# nixieWatchV0.net
KiCad netlist of a schematic drawn in EAGLE
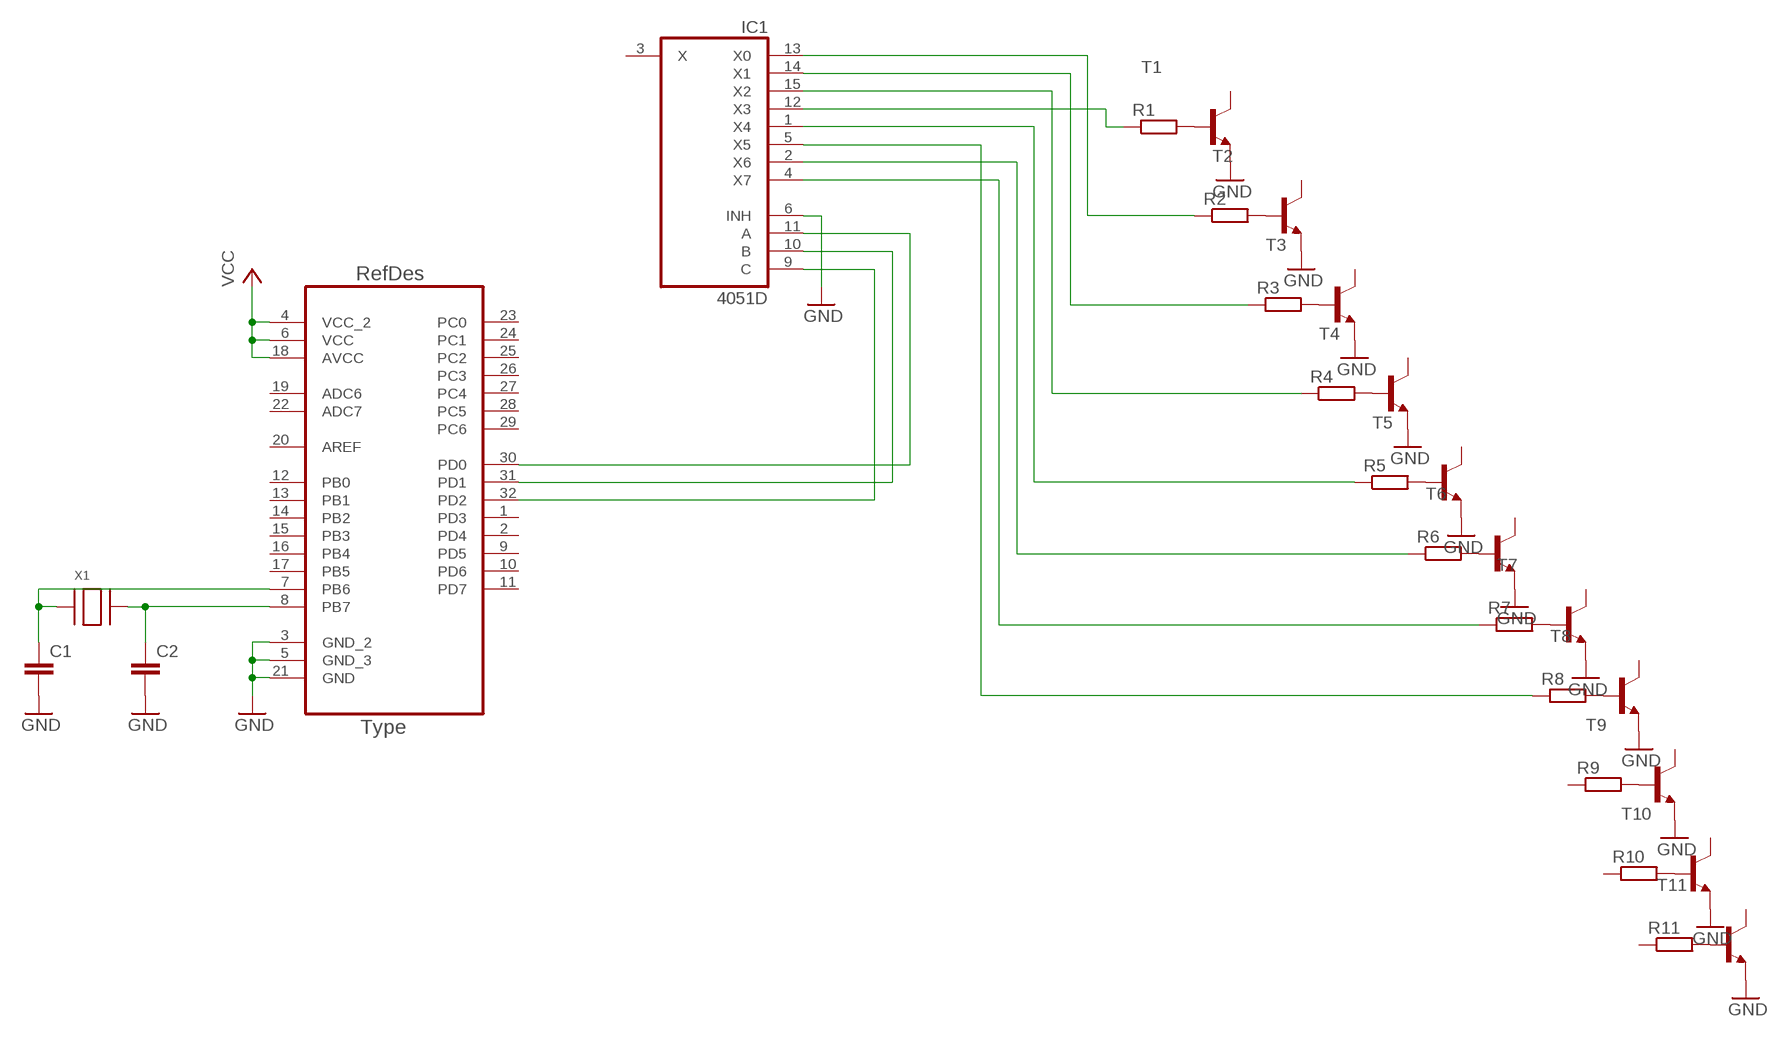
[diagram p0: schematic, sheet 1]

(export (version "E")
  (design (tool "Eeschema 10.0.6"))
  (components
    (comp (ref "C1")
      (value "C-EUC0402")
      (footprint "eagle-import:C0402")
      (libsource (lib "eagle-import") (part "C-EUC0402"))
    )
    (comp (ref "C2")
      (value "C-EUC0402")
      (footprint "eagle-import:C0402")
      (libsource (lib "eagle-import") (part "C-EUC0402"))
    )
    (comp (ref "IC1")
      (value "4051D")
      (footprint "eagle-import:SO16")
      (libsource (lib "eagle-import") (part "4051D"))
    )
    (comp (ref "R1")
      (value "R-EU_M1206")
      (footprint "eagle-import:M1206")
      (libsource (lib "eagle-import") (part "R-EU_M1206"))
    )
    (comp (ref "R2")
      (value "R-EU_M1206")
      (footprint "eagle-import:M1206")
      (libsource (lib "eagle-import") (part "R-EU_M1206"))
    )
    (comp (ref "R3")
      (value "R-EU_M1206")
      (footprint "eagle-import:M1206")
      (libsource (lib "eagle-import") (part "R-EU_M1206"))
    )
    (comp (ref "R4")
      (value "R-EU_M1206")
      (footprint "eagle-import:M1206")
      (libsource (lib "eagle-import") (part "R-EU_M1206"))
    )
    (comp (ref "R5")
      (value "R-EU_M1206")
      (footprint "eagle-import:M1206")
      (libsource (lib "eagle-import") (part "R-EU_M1206"))
    )
    (comp (ref "R6")
      (value "R-EU_M1206")
      (footprint "eagle-import:M1206")
      (libsource (lib "eagle-import") (part "R-EU_M1206"))
    )
    (comp (ref "R7")
      (value "R-EU_M1206")
      (footprint "eagle-import:M1206")
      (libsource (lib "eagle-import") (part "R-EU_M1206"))
    )
    (comp (ref "R8")
      (value "R-EU_M1206")
      (footprint "eagle-import:M1206")
      (libsource (lib "eagle-import") (part "R-EU_M1206"))
    )
    (comp (ref "R9")
      (value "R-EU_M1206")
      (footprint "eagle-import:M1206")
      (libsource (lib "eagle-import") (part "R-EU_M1206"))
    )
    (comp (ref "R10")
      (value "R-EU_M1206")
      (footprint "eagle-import:M1206")
      (libsource (lib "eagle-import") (part "R-EU_M1206"))
    )
    (comp (ref "R11")
      (value "R-EU_M1206")
      (footprint "eagle-import:M1206")
      (libsource (lib "eagle-import") (part "R-EU_M1206"))
    )
    (comp (ref "T1")
      (value "-NPN-SOT23-EBC")
      (footprint "eagle-import:SOT23-EBC")
      (libsource (lib "eagle-import") (part "-NPN-SOT23-EBC"))
    )
    (comp (ref "T2")
      (value "-NPN-SOT23-EBC")
      (footprint "eagle-import:SOT23-EBC")
      (libsource (lib "eagle-import") (part "-NPN-SOT23-EBC"))
    )
    (comp (ref "T3")
      (value "-NPN-SOT23-EBC")
      (footprint "eagle-import:SOT23-EBC")
      (libsource (lib "eagle-import") (part "-NPN-SOT23-EBC"))
    )
    (comp (ref "T4")
      (value "-NPN-SOT23-EBC")
      (footprint "eagle-import:SOT23-EBC")
      (libsource (lib "eagle-import") (part "-NPN-SOT23-EBC"))
    )
    (comp (ref "T5")
      (value "-NPN-SOT23-EBC")
      (footprint "eagle-import:SOT23-EBC")
      (libsource (lib "eagle-import") (part "-NPN-SOT23-EBC"))
    )
    (comp (ref "T6")
      (value "-NPN-SOT23-EBC")
      (footprint "eagle-import:SOT23-EBC")
      (libsource (lib "eagle-import") (part "-NPN-SOT23-EBC"))
    )
    (comp (ref "T7")
      (value "-NPN-SOT23-EBC")
      (footprint "eagle-import:SOT23-EBC")
      (libsource (lib "eagle-import") (part "-NPN-SOT23-EBC"))
    )
    (comp (ref "T8")
      (value "-NPN-SOT23-EBC")
      (footprint "eagle-import:SOT23-EBC")
      (libsource (lib "eagle-import") (part "-NPN-SOT23-EBC"))
    )
    (comp (ref "T9")
      (value "-NPN-SOT23-EBC")
      (footprint "eagle-import:SOT23-EBC")
      (libsource (lib "eagle-import") (part "-NPN-SOT23-EBC"))
    )
    (comp (ref "T10")
      (value "-NPN-SOT23-EBC")
      (footprint "eagle-import:SOT23-EBC")
      (libsource (lib "eagle-import") (part "-NPN-SOT23-EBC"))
    )
    (comp (ref "T11")
      (value "-NPN-SOT23-EBC")
      (footprint "eagle-import:SOT23-EBC")
      (libsource (lib "eagle-import") (part "-NPN-SOT23-EBC"))
    )
    (comp (ref "U1")
      (value "ATMEGA328P-AU")
      (footprint "eagle-import:QFP80P900X900X120-32N")
      (libsource (lib "eagle-import") (part "ATMEGA328P-AU"))
    )
    (comp (ref "X1")
      (value "XTAL-3.2X1.5")
      (footprint "eagle-import:XTAL3215")
      (libsource (lib "eagle-import") (part "XTAL-3.2X1.5"))
    )
  )
  (nets
    (net (code "1") (name "GND") (class "Default")
      (node (ref "C1") (pin "2") (pinfunction "2_2") (pintype "passive"))
      (node (ref "C2") (pin "2") (pinfunction "2_2") (pintype "passive"))
      (node (ref "IC1") (pin "6") (pinfunction "INH_6") (pintype "input"))
      (node (ref "T1") (pin "E") (pinfunction "E_E") (pintype "passive"))
      (node (ref "T10") (pin "E") (pinfunction "E_E") (pintype "passive"))
      (node (ref "T11") (pin "E") (pinfunction "E_E") (pintype "passive"))
      (node (ref "T2") (pin "E") (pinfunction "E_E") (pintype "passive"))
      (node (ref "T3") (pin "E") (pinfunction "E_E") (pintype "passive"))
      (node (ref "T4") (pin "E") (pinfunction "E_E") (pintype "passive"))
      (node (ref "T5") (pin "E") (pinfunction "E_E") (pintype "passive"))
      (node (ref "T6") (pin "E") (pinfunction "E_E") (pintype "passive"))
      (node (ref "T7") (pin "E") (pinfunction "E_E") (pintype "passive"))
      (node (ref "T8") (pin "E") (pinfunction "E_E") (pintype "passive"))
      (node (ref "T9") (pin "E") (pinfunction "E_E") (pintype "passive"))
      (node (ref "U1") (pin "21") (pinfunction "GND_21") (pintype "passive"))
      (node (ref "U1") (pin "3") (pinfunction "GND_2_3") (pintype "passive"))
      (node (ref "U1") (pin "5") (pinfunction "GND_3_5") (pintype "passive"))
    )
    (net (code "2") (name "Net-(IC1A-A)") (class "Default")
      (node (ref "IC1") (pin "11") (pinfunction "A_11") (pintype "input"))
      (node (ref "U1") (pin "30") (pinfunction "PD0_30") (pintype "bidirectional"))
    )
    (net (code "3") (name "Net-(IC1A-B)") (class "Default")
      (node (ref "IC1") (pin "10") (pinfunction "B_10") (pintype "input"))
      (node (ref "U1") (pin "31") (pinfunction "PD1_31") (pintype "bidirectional"))
    )
    (net (code "4") (name "Net-(IC1A-C)") (class "Default")
      (node (ref "IC1") (pin "9") (pinfunction "C_9") (pintype "input"))
      (node (ref "U1") (pin "32") (pinfunction "PD2_32") (pintype "bidirectional"))
    )
    (net (code "5") (name "Net-(IC1A-X0)") (class "Default")
      (node (ref "IC1") (pin "13") (pinfunction "X0_13") (pintype "bidirectional"))
      (node (ref "R2") (pin "1") (pinfunction "1_1") (pintype "passive"))
    )
    (net (code "6") (name "Net-(IC1A-X1)") (class "Default")
      (node (ref "IC1") (pin "14") (pinfunction "X1_14") (pintype "bidirectional"))
      (node (ref "R3") (pin "1") (pinfunction "1_1") (pintype "passive"))
    )
    (net (code "7") (name "Net-(IC1A-X2)") (class "Default")
      (node (ref "IC1") (pin "15") (pinfunction "X2_15") (pintype "bidirectional"))
      (node (ref "R4") (pin "1") (pinfunction "1_1") (pintype "passive"))
    )
    (net (code "8") (name "Net-(IC1A-X3)") (class "Default")
      (node (ref "IC1") (pin "12") (pinfunction "X3_12") (pintype "bidirectional"))
      (node (ref "R1") (pin "1") (pinfunction "1_1") (pintype "passive"))
    )
    (net (code "9") (name "Net-(IC1A-X4)") (class "Default")
      (node (ref "IC1") (pin "1") (pinfunction "X4_1") (pintype "bidirectional"))
      (node (ref "R5") (pin "1") (pinfunction "1_1") (pintype "passive"))
    )
    (net (code "10") (name "Net-(IC1A-X5)") (class "Default")
      (node (ref "IC1") (pin "5") (pinfunction "X5_5") (pintype "bidirectional"))
      (node (ref "R8") (pin "1") (pinfunction "1_1") (pintype "passive"))
    )
    (net (code "11") (name "Net-(IC1A-X6)") (class "Default")
      (node (ref "IC1") (pin "2") (pinfunction "X6_2") (pintype "bidirectional"))
      (node (ref "R6") (pin "1") (pinfunction "1_1") (pintype "passive"))
    )
    (net (code "12") (name "Net-(IC1A-X7)") (class "Default")
      (node (ref "IC1") (pin "4") (pinfunction "X7_4") (pintype "bidirectional"))
      (node (ref "R7") (pin "1") (pinfunction "1_1") (pintype "passive"))
    )
    (net (code "13") (name "Net-(R1-Pad2)") (class "Default")
      (node (ref "R1") (pin "2") (pinfunction "2_2") (pintype "passive"))
      (node (ref "T1") (pin "B") (pinfunction "B_B") (pintype "passive"))
    )
    (net (code "14") (name "Net-(R2-Pad2)") (class "Default")
      (node (ref "R2") (pin "2") (pinfunction "2_2") (pintype "passive"))
      (node (ref "T2") (pin "B") (pinfunction "B_B") (pintype "passive"))
    )
    (net (code "15") (name "Net-(R3-Pad2)") (class "Default")
      (node (ref "R3") (pin "2") (pinfunction "2_2") (pintype "passive"))
      (node (ref "T3") (pin "B") (pinfunction "B_B") (pintype "passive"))
    )
    (net (code "16") (name "Net-(R4-Pad2)") (class "Default")
      (node (ref "R4") (pin "2") (pinfunction "2_2") (pintype "passive"))
      (node (ref "T4") (pin "B") (pinfunction "B_B") (pintype "passive"))
    )
    (net (code "17") (name "Net-(R5-Pad2)") (class "Default")
      (node (ref "R5") (pin "2") (pinfunction "2_2") (pintype "passive"))
      (node (ref "T5") (pin "B") (pinfunction "B_B") (pintype "passive"))
    )
    (net (code "18") (name "Net-(R6-Pad2)") (class "Default")
      (node (ref "R6") (pin "2") (pinfunction "2_2") (pintype "passive"))
      (node (ref "T6") (pin "B") (pinfunction "B_B") (pintype "passive"))
    )
    (net (code "19") (name "Net-(R7-Pad2)") (class "Default")
      (node (ref "R7") (pin "2") (pinfunction "2_2") (pintype "passive"))
      (node (ref "T7") (pin "B") (pinfunction "B_B") (pintype "passive"))
    )
    (net (code "20") (name "Net-(R8-Pad2)") (class "Default")
      (node (ref "R8") (pin "2") (pinfunction "2_2") (pintype "passive"))
      (node (ref "T8") (pin "B") (pinfunction "B_B") (pintype "passive"))
    )
    (net (code "21") (name "Net-(R9-Pad2)") (class "Default")
      (node (ref "R9") (pin "2") (pinfunction "2_2") (pintype "passive"))
      (node (ref "T9") (pin "B") (pinfunction "B_B") (pintype "passive"))
    )
    (net (code "22") (name "Net-(R10-Pad2)") (class "Default")
      (node (ref "R10") (pin "2") (pinfunction "2_2") (pintype "passive"))
      (node (ref "T10") (pin "B") (pinfunction "B_B") (pintype "passive"))
    )
    (net (code "23") (name "Net-(R11-Pad2)") (class "Default")
      (node (ref "R11") (pin "2") (pinfunction "2_2") (pintype "passive"))
      (node (ref "T11") (pin "B") (pinfunction "B_B") (pintype "passive"))
    )
    (net (code "24") (name "Net-(U1-PB6)") (class "Default")
      (node (ref "C1") (pin "1") (pinfunction "1_1") (pintype "passive"))
      (node (ref "U1") (pin "7") (pinfunction "PB6_7") (pintype "bidirectional"))
      (node (ref "X1") (pin "P$1") (pinfunction "P$1_P$1") (pintype "bidirectional"))
    )
    (net (code "25") (name "Net-(U1-PB7)") (class "Default")
      (node (ref "C2") (pin "1") (pinfunction "1_1") (pintype "passive"))
      (node (ref "U1") (pin "8") (pinfunction "PB7_8") (pintype "bidirectional"))
      (node (ref "X1") (pin "P$2") (pinfunction "P$2_P$2") (pintype "bidirectional"))
    )
    (net (code "26") (name "VCC") (class "Default")
      (node (ref "U1") (pin "18") (pinfunction "AVCC_18") (pintype "power_in"))
      (node (ref "U1") (pin "4") (pinfunction "VCC_2_4") (pintype "power_in"))
      (node (ref "U1") (pin "6") (pinfunction "VCC_6") (pintype "power_in"))
    )
    (net (code "27") (name "unconnected-(IC1A-X-Pad3)") (class "Default")
      (node (ref "IC1") (pin "3") (pinfunction "X_3") (pintype "bidirectional"))
    )
    (net (code "28") (name "unconnected-(R9-Pad1)") (class "Default")
      (node (ref "R9") (pin "1") (pinfunction "1_1") (pintype "passive"))
    )
    (net (code "29") (name "unconnected-(R10-Pad1)") (class "Default")
      (node (ref "R10") (pin "1") (pinfunction "1_1") (pintype "passive"))
    )
    (net (code "30") (name "unconnected-(R11-Pad1)") (class "Default")
      (node (ref "R11") (pin "1") (pinfunction "1_1") (pintype "passive"))
    )
    (net (code "31") (name "unconnected-(T1-PadC)") (class "Default")
      (node (ref "T1") (pin "C") (pinfunction "C_C") (pintype "passive"))
    )
    (net (code "32") (name "unconnected-(T2-PadC)") (class "Default")
      (node (ref "T2") (pin "C") (pinfunction "C_C") (pintype "passive"))
    )
    (net (code "33") (name "unconnected-(T3-PadC)") (class "Default")
      (node (ref "T3") (pin "C") (pinfunction "C_C") (pintype "passive"))
    )
    (net (code "34") (name "unconnected-(T4-PadC)") (class "Default")
      (node (ref "T4") (pin "C") (pinfunction "C_C") (pintype "passive"))
    )
    (net (code "35") (name "unconnected-(T5-PadC)") (class "Default")
      (node (ref "T5") (pin "C") (pinfunction "C_C") (pintype "passive"))
    )
    (net (code "36") (name "unconnected-(T6-PadC)") (class "Default")
      (node (ref "T6") (pin "C") (pinfunction "C_C") (pintype "passive"))
    )
    (net (code "37") (name "unconnected-(T7-PadC)") (class "Default")
      (node (ref "T7") (pin "C") (pinfunction "C_C") (pintype "passive"))
    )
    (net (code "38") (name "unconnected-(T8-PadC)") (class "Default")
      (node (ref "T8") (pin "C") (pinfunction "C_C") (pintype "passive"))
    )
    (net (code "39") (name "unconnected-(T9-PadC)") (class "Default")
      (node (ref "T9") (pin "C") (pinfunction "C_C") (pintype "passive"))
    )
    (net (code "40") (name "unconnected-(T10-PadC)") (class "Default")
      (node (ref "T10") (pin "C") (pinfunction "C_C") (pintype "passive"))
    )
    (net (code "41") (name "unconnected-(T11-PadC)") (class "Default")
      (node (ref "T11") (pin "C") (pinfunction "C_C") (pintype "passive"))
    )
    (net (code "42") (name "unconnected-(U1-ADC6-Pad19)") (class "Default")
      (node (ref "U1") (pin "19") (pinfunction "ADC6_19") (pintype "input"))
    )
    (net (code "43") (name "unconnected-(U1-ADC7-Pad22)") (class "Default")
      (node (ref "U1") (pin "22") (pinfunction "ADC7_22") (pintype "input"))
    )
    (net (code "44") (name "unconnected-(U1-AREF-Pad20)") (class "Default")
      (node (ref "U1") (pin "20") (pinfunction "AREF_20") (pintype "input"))
    )
    (net (code "45") (name "unconnected-(U1-PB0-Pad12)") (class "Default")
      (node (ref "U1") (pin "12") (pinfunction "PB0_12") (pintype "bidirectional"))
    )
    (net (code "46") (name "unconnected-(U1-PB1-Pad13)") (class "Default")
      (node (ref "U1") (pin "13") (pinfunction "PB1_13") (pintype "bidirectional"))
    )
    (net (code "47") (name "unconnected-(U1-PB2-Pad14)") (class "Default")
      (node (ref "U1") (pin "14") (pinfunction "PB2_14") (pintype "bidirectional"))
    )
    (net (code "48") (name "unconnected-(U1-PB3-Pad15)") (class "Default")
      (node (ref "U1") (pin "15") (pinfunction "PB3_15") (pintype "bidirectional"))
    )
    (net (code "49") (name "unconnected-(U1-PB4-Pad16)") (class "Default")
      (node (ref "U1") (pin "16") (pinfunction "PB4_16") (pintype "bidirectional"))
    )
    (net (code "50") (name "unconnected-(U1-PB5-Pad17)") (class "Default")
      (node (ref "U1") (pin "17") (pinfunction "PB5_17") (pintype "bidirectional"))
    )
    (net (code "51") (name "unconnected-(U1-PC0-Pad23)") (class "Default")
      (node (ref "U1") (pin "23") (pinfunction "PC0_23") (pintype "bidirectional"))
    )
    (net (code "52") (name "unconnected-(U1-PC1-Pad24)") (class "Default")
      (node (ref "U1") (pin "24") (pinfunction "PC1_24") (pintype "bidirectional"))
    )
    (net (code "53") (name "unconnected-(U1-PC2-Pad25)") (class "Default")
      (node (ref "U1") (pin "25") (pinfunction "PC2_25") (pintype "bidirectional"))
    )
    (net (code "54") (name "unconnected-(U1-PC3-Pad26)") (class "Default")
      (node (ref "U1") (pin "26") (pinfunction "PC3_26") (pintype "bidirectional"))
    )
    (net (code "55") (name "unconnected-(U1-PC4-Pad27)") (class "Default")
      (node (ref "U1") (pin "27") (pinfunction "PC4_27") (pintype "bidirectional"))
    )
    (net (code "56") (name "unconnected-(U1-PC5-Pad28)") (class "Default")
      (node (ref "U1") (pin "28") (pinfunction "PC5_28") (pintype "bidirectional"))
    )
    (net (code "57") (name "unconnected-(U1-PC6-Pad29)") (class "Default")
      (node (ref "U1") (pin "29") (pinfunction "PC6_29") (pintype "bidirectional"))
    )
    (net (code "58") (name "unconnected-(U1-PD3-Pad1)") (class "Default")
      (node (ref "U1") (pin "1") (pinfunction "PD3_1") (pintype "bidirectional"))
    )
    (net (code "59") (name "unconnected-(U1-PD4-Pad2)") (class "Default")
      (node (ref "U1") (pin "2") (pinfunction "PD4_2") (pintype "bidirectional"))
    )
    (net (code "60") (name "unconnected-(U1-PD5-Pad9)") (class "Default")
      (node (ref "U1") (pin "9") (pinfunction "PD5_9") (pintype "bidirectional"))
    )
    (net (code "61") (name "unconnected-(U1-PD6-Pad10)") (class "Default")
      (node (ref "U1") (pin "10") (pinfunction "PD6_10") (pintype "bidirectional"))
    )
    (net (code "62") (name "unconnected-(U1-PD7-Pad11)") (class "Default")
      (node (ref "U1") (pin "11") (pinfunction "PD7_11") (pintype "bidirectional"))
    )
  )
)
